# CAN_IF.net
KiCad netlist of a schematic drawn in Altium Designer
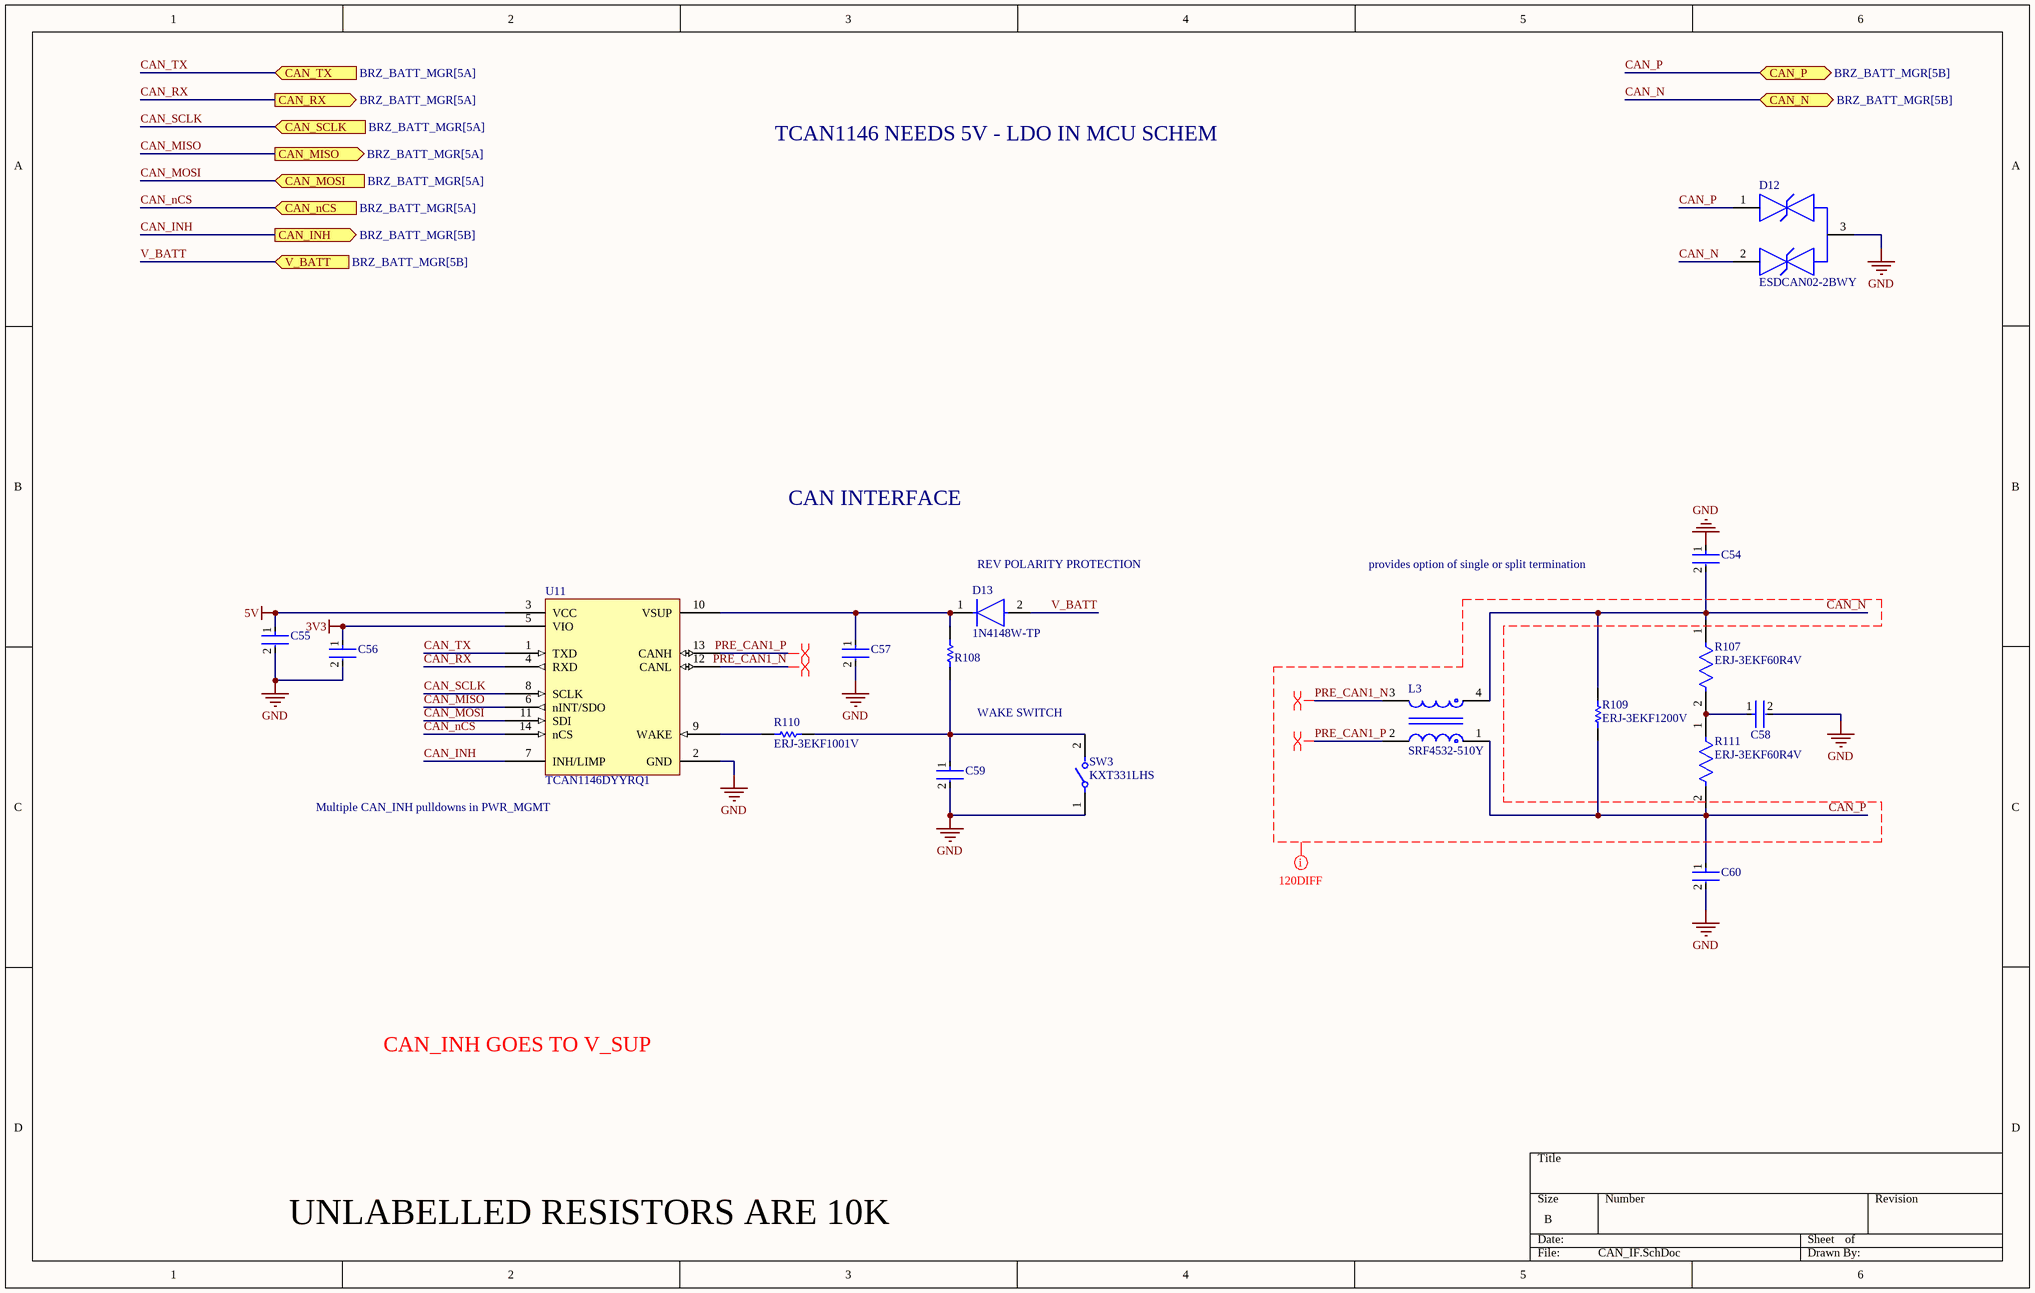
[diagram p0: CAN_IF.SchDoc]

(export (version "E")
  (design (tool "Eeschema 10.0.6"))
  (components
    (comp (ref "C54")
      (value "6.6p 10v")
      (footprint "FP-0402-L_1_0_0_05-W_0_5-IPC_A")
      (description "LARGE PADS, 0402 CAP, CHANGE COMMENT TO MATCH REAL P/N")
      (libsource (lib "Space Concordia") (part "b4654b650e69147ec39a6b967a45e02"))
    )
    (comp (ref "C55")
      (value "100n 10v")
      (footprint "FP-0402-L_1_0_0_05-W_0_5-IPC_A")
      (description "LARGE PADS, 0402 CAP, CHANGE COMMENT TO MATCH REAL P/N")
      (libsource (lib "Space Concordia") (part "b4654b650e69147ec39a6b967a45e02"))
    )
    (comp (ref "C56")
      (value "100n 10v")
      (footprint "FP-0402-L_1_0_0_05-W_0_5-IPC_A")
      (description "LARGE PADS, 0402 CAP, CHANGE COMMENT TO MATCH REAL P/N")
      (libsource (lib "Space Concordia") (part "b4654b650e69147ec39a6b967a45e02"))
    )
    (comp (ref "C57")
      (value "100n 10v")
      (footprint "FP-0402-L_1_0_0_05-W_0_5-IPC_A")
      (description "LARGE PADS, 0402 CAP, CHANGE COMMENT TO MATCH REAL P/N")
      (libsource (lib "Space Concordia") (part "b4654b650e69147ec39a6b967a45e02"))
    )
    (comp (ref "C58")
      (value "100n 10v")
      (footprint "FP-0402-L_1_0_0_05-W_0_5-IPC_A")
      (description "LARGE PADS, 0402 CAP, CHANGE COMMENT TO MATCH REAL P/N")
      (libsource (lib "Space Concordia") (part "b4654b650e69147ec39a6b967a45e02"))
    )
    (comp (ref "C59")
      (value "100n 10v")
      (footprint "FP-0402-L_1_0_0_05-W_0_5-IPC_A")
      (description "LARGE PADS, 0402 CAP, CHANGE COMMENT TO MATCH REAL P/N")
      (libsource (lib "Space Concordia") (part "b4654b650e69147ec39a6b967a45e02"))
    )
    (comp (ref "C60")
      (value "6.6p 10v")
      (footprint "FP-0402-L_1_0_0_05-W_0_5-IPC_A")
      (description "LARGE PADS, 0402 CAP, CHANGE COMMENT TO MATCH REAL P/N")
      (libsource (lib "Space Concordia") (part "b4654b650e69147ec39a6b967a45e02"))
    )
    (comp (ref "D12")
      (value "ESDCAN02-2BWY")
      (footprint "FP-SOT323-3L-MFG")
      (description "TVS DIODE 26.5V 44V SOT323-3")
      (fields
        (field (name "MANUFACTURER") "STMicroelectronics")
        (field (name "OCTOPART") "https://octopart.com/esdcan02-2bwy-stmicroelectronics-58631133")
      )
      (libsource (lib "Altium Content Vault") (part "0b9019fb5e52ed66df21ec1535be59d"))
    )
    (comp (ref "D13")
      (value "1N4148W-TP")
      (footprint "FP-SOD-123-IPC_A")
      (description "DIODE GEN PURP 100V 150MA SOD123")
      (libsource (lib "Altium Content Vault") (part "d7152d700b627762746794eb795d46e"))
    )
    (comp (ref "L3")
      (value "SRF4532-510Y")
      (footprint "FP-SRF4532-MFG")
      (description "CMC 51UH 200MA 2LN 2KOHM SMD")
      (fields (field (name "TOLERANCE") "50%"))
      (libsource (lib "Altium Content Vault") (part "aca3f6a10b859f211cca95010157f3b"))
    )
    (comp (ref "R107")
      (value "ERJ-3EKF60R4V")
      (footprint "FP-ERJ3EK-IPC_C")
      (description "RES SMD 60.4 OHM 1% 1/10W 0603")
      (fields (field (name "TOLERANCE") "1%"))
      (libsource (lib "Altium Content Vault") (part "1029c3af85768c4190bb7ad29bc67b5"))
    )
    (comp (ref "R108")
      (value "ERJ3EKF1002V")
      (footprint "RESC1609X55X30LL15T15")
      (description "Chip Resistor, 10 KOhm, +/- 1%, 0.1 W, -55 to 155 degC, 0603 (1608 Metric), RoHS, Tape and Reel")
      (fields (field (name "TOLERANCE") "1%") (field (name "MANUFACTURER") "Panasonic"))
      (libsource (lib "Altium Content Vault") (part "RES-2"))
    )
    (comp (ref "R109")
      (value "ERJ-3EKF1200V")
      (footprint "RESC1609X55X30ML15T15")
      (description "Chip Resistor, 120 Ohm, +/- 1%, 0.1 W, -55 to 155 degC, 0603 (1608 Metric), RoHS, Tape and Reel")
      (fields (field (name "TOLERANCE") "1%") (field (name "MANUFACTURER") "Panasonic"))
      (libsource (lib "Altium Content Vault") (part "RES-2"))
    )
    (comp (ref "R110")
      (value "ERJ-3EKF1001V")
      (footprint "RESC1608X55X30LL15T15")
      (fields (field (name "MANUFACTURER") "Panasonic"))
      (libsource (lib "Altium Content Vault") (part "RES"))
    )
    (comp (ref "R111")
      (value "ERJ-3EKF60R4V")
      (footprint "FP-ERJ3EK-IPC_C")
      (description "RES SMD 60.4 OHM 1% 1/10W 0603")
      (fields (field (name "TOLERANCE") "1%"))
      (libsource (lib "Altium Content Vault") (part "1029c3af85768c4190bb7ad29bc67b5"))
    )
    (comp (ref "SW3")
      (value "KXT331LHS")
      (footprint "FP-KXT331LHS-MFG")
      (description "SWITCH TACTILE SPST-NO 0.02A 15V")
      (libsource (lib "Altium Content Vault") (part "bb27bde45df87f1f469753f287ef5ae"))
    )
    (comp (ref "U11")
      (value "TCAN1146DYYRQ1")
      (footprint "TCAN1146DYYRQ1-Footprint-1")
      (libsource (lib "uORocketry Hardware") (part "TCAN1146DYYRQ1"))
    )
  )
  (nets
    (net (code "1") (name "/CAN_INH") (class "Default")
      (node (ref "U11") (pin "7") (pinfunction "INH/LIMP_7") (pintype "passive"))
    )
    (net (code "2") (name "/CAN_MISO") (class "Default")
      (node (ref "U11") (pin "6") (pinfunction "nINT/SDO_6") (pintype "output"))
    )
    (net (code "3") (name "/CAN_MOSI") (class "Default")
      (node (ref "U11") (pin "11") (pinfunction "SDI_11") (pintype "input"))
    )
    (net (code "4") (name "/CAN_N") (class "Default")
      (node (ref "C54") (pin "2") (pinfunction "2_2") (pintype "passive"))
      (node (ref "D12") (pin "2") (pinfunction "2_2") (pintype "passive"))
      (node (ref "L3") (pin "4") (pinfunction "4_4") (pintype "passive"))
      (node (ref "R107") (pin "1") (pinfunction "1_1") (pintype "passive"))
      (node (ref "R109") (pin "1") (pinfunction "1_1") (pintype "passive"))
    )
    (net (code "5") (name "/CAN_P") (class "Default")
      (node (ref "C60") (pin "1") (pinfunction "1_1") (pintype "passive"))
      (node (ref "D12") (pin "1") (pinfunction "1_1") (pintype "passive"))
      (node (ref "L3") (pin "1") (pinfunction "1_1") (pintype "passive"))
      (node (ref "R109") (pin "2") (pinfunction "2_2") (pintype "passive"))
      (node (ref "R111") (pin "2") (pinfunction "2_2") (pintype "passive"))
    )
    (net (code "6") (name "/CAN_RX") (class "Default")
      (node (ref "U11") (pin "4") (pinfunction "RXD_4") (pintype "output"))
    )
    (net (code "7") (name "/CAN_SCLK") (class "Default")
      (node (ref "U11") (pin "8") (pinfunction "SCLK_8") (pintype "input"))
    )
    (net (code "8") (name "/CAN_TX") (class "Default")
      (node (ref "U11") (pin "1") (pinfunction "TXD_1") (pintype "input"))
    )
    (net (code "9") (name "/CAN_nCS") (class "Default")
      (node (ref "U11") (pin "14") (pinfunction "nCS_14") (pintype "input"))
    )
    (net (code "10") (name "/PRE_CAN1_N") (class "Default")
      (node (ref "L3") (pin "3") (pinfunction "3_3") (pintype "passive"))
      (node (ref "U11") (pin "12") (pinfunction "CANL_12") (pintype "bidirectional"))
    )
    (net (code "11") (name "/PRE_CAN1_P") (class "Default")
      (node (ref "L3") (pin "2") (pinfunction "2_2") (pintype "passive"))
      (node (ref "U11") (pin "13") (pinfunction "CANH_13") (pintype "bidirectional"))
    )
    (net (code "12") (name "/V_BATT") (class "Default")
      (node (ref "D13") (pin "2") (pinfunction "A_2") (pintype "passive"))
    )
    (net (code "13") (name "3V3") (class "Default")
      (node (ref "C56") (pin "1") (pinfunction "1_1") (pintype "passive"))
      (node (ref "U11") (pin "5") (pinfunction "VIO_5") (pintype "power_in"))
    )
    (net (code "14") (name "5V") (class "Default")
      (node (ref "C55") (pin "1") (pinfunction "1_1") (pintype "passive"))
      (node (ref "U11") (pin "3") (pinfunction "VCC_3") (pintype "power_in"))
    )
    (net (code "15") (name "GND") (class "Default")
      (node (ref "C54") (pin "1") (pinfunction "1_1") (pintype "passive"))
      (node (ref "C55") (pin "2") (pinfunction "2_2") (pintype "passive"))
      (node (ref "C56") (pin "2") (pinfunction "2_2") (pintype "passive"))
      (node (ref "C57") (pin "2") (pinfunction "2_2") (pintype "passive"))
      (node (ref "C58") (pin "2") (pinfunction "2_2") (pintype "passive"))
      (node (ref "C59") (pin "2") (pinfunction "2_2") (pintype "passive"))
      (node (ref "C60") (pin "2") (pinfunction "2_2") (pintype "passive"))
      (node (ref "D12") (pin "3") (pinfunction "3_3") (pintype "passive"))
      (node (ref "SW3") (pin "1") (pinfunction "1_1") (pintype "passive"))
      (node (ref "U11") (pin "2") (pinfunction "GND_2") (pintype "power_in"))
    )
    (net (code "16") (name "Net-(C58-Pad1)") (class "Default")
      (node (ref "C58") (pin "1") (pinfunction "1_1") (pintype "passive"))
      (node (ref "R107") (pin "2") (pinfunction "2_2") (pintype "passive"))
      (node (ref "R111") (pin "1") (pinfunction "1_1") (pintype "passive"))
    )
    (net (code "17") (name "Net-(C59-Pad1)") (class "Default")
      (node (ref "C59") (pin "1") (pinfunction "1_1") (pintype "passive"))
      (node (ref "R108") (pin "2") (pinfunction "2_2") (pintype "passive"))
      (node (ref "R110") (pin "2") (pinfunction "2_2") (pintype "passive"))
      (node (ref "SW3") (pin "2") (pinfunction "2_2") (pintype "passive"))
    )
    (net (code "18") (name "Net-(D13-C)") (class "Default")
      (node (ref "C57") (pin "1") (pinfunction "1_1") (pintype "passive"))
      (node (ref "D13") (pin "1") (pinfunction "C_1") (pintype "passive"))
      (node (ref "R108") (pin "1") (pinfunction "1_1") (pintype "passive"))
      (node (ref "U11") (pin "10") (pinfunction "VSUP_10") (pintype "power_in"))
    )
    (net (code "19") (name "Net-(U11-WAKE)") (class "Default")
      (node (ref "R110") (pin "1") (pinfunction "1_1") (pintype "passive"))
      (node (ref "U11") (pin "9") (pinfunction "WAKE_9") (pintype "input"))
    )
  )
)
